# Connectors.net
KiCad netlist of a schematic drawn in Altium Designer
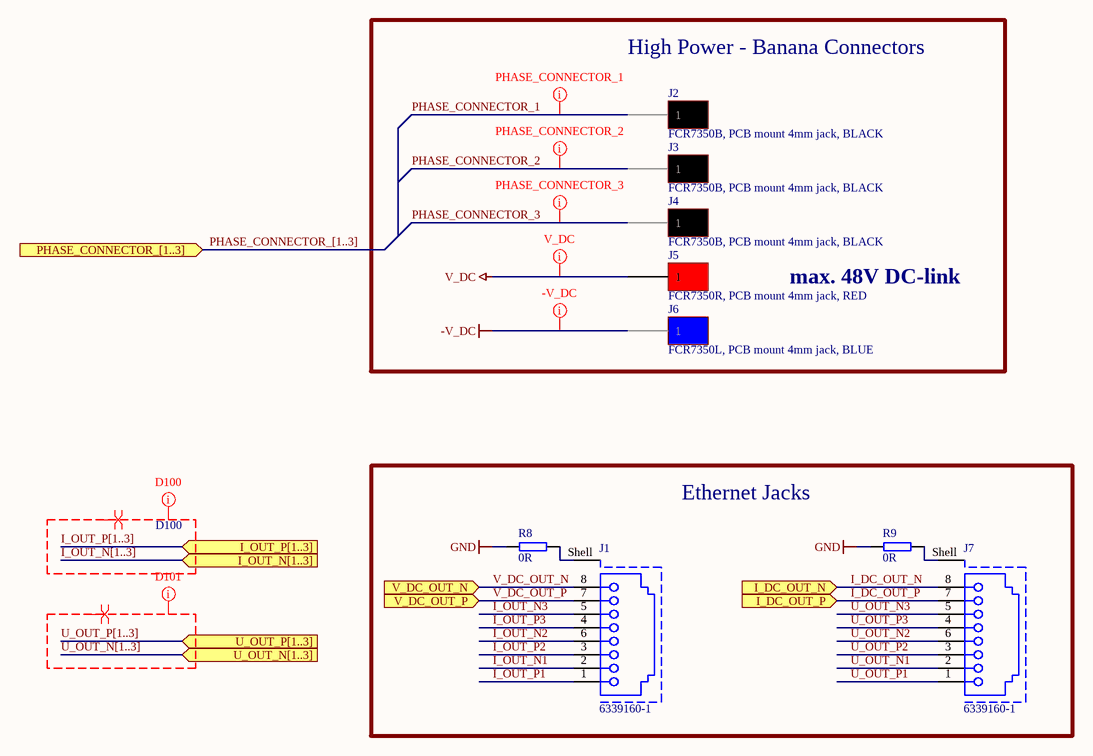
[diagram p0: Connectors.SchDoc]

(export (version "E")
  (design (tool "Eeschema 10.0.6"))
  (components
    (comp (ref "J1")
      (value "6339160-1")
      (footprint "634008149821")
      (fields
        (field (name "MANUFACTURER") "TE")
        (field (name "LCSC PART NUMBER") "C125076")
        (field (name "CREATED FROM") "NDiringer")
      )
      (libsource (lib "user") (part "634008149821"))
    )
    (comp (ref "J2")
      (value "FCR7350B, PCB mount 4mm jack, BLACK")
      (footprint "FCR7350")
      (description "FCR7350B, 1000V, 24A, BLACK")
      (fields
        (field (name "MANUFACTURER PART NUMBER") "FCR7350B")
        (field (name "MANUFACTURER") "Cliff")
        (field (name "CREATED FROM") "DHufnagel")
      )
      (libsource (lib "user") (part "FCR7350B"))
    )
    (comp (ref "J3")
      (value "FCR7350B, PCB mount 4mm jack, BLACK")
      (footprint "FCR7350")
      (description "FCR7350B, 1000V, 24A, BLACK")
      (fields
        (field (name "MANUFACTURER PART NUMBER") "FCR7350B")
        (field (name "MANUFACTURER") "Cliff")
        (field (name "CREATED FROM") "DHufnagel")
      )
      (libsource (lib "user") (part "FCR7350B"))
    )
    (comp (ref "J4")
      (value "FCR7350B, PCB mount 4mm jack, BLACK")
      (footprint "FCR7350")
      (description "FCR7350B, 1000V, 24A, BLACK")
      (fields
        (field (name "MANUFACTURER PART NUMBER") "FCR7350B")
        (field (name "MANUFACTURER") "Cliff")
        (field (name "CREATED FROM") "DHufnagel")
      )
      (libsource (lib "user") (part "FCR7350B"))
    )
    (comp (ref "J5")
      (value "FCR7350R, PCB mount 4mm jack, RED")
      (footprint "FCR7350")
      (description "FCR7350B, 1000V, 24A, RED")
      (fields
        (field (name "MANUFACTURER PART NUMBER") "FCR7350R")
        (field (name "MANUFACTURER") "Cliff")
        (field (name "CREATED FROM") "DHufnagel")
      )
      (libsource (lib "user") (part "FCR7350R"))
    )
    (comp (ref "J6")
      (value "FCR7350L, PCB mount 4mm jack, BLUE")
      (footprint "FCR7350")
      (description "FCR7350B, 1000V, 24A, BLUE")
      (fields
        (field (name "MANUFACTURER PART NUMBER") "FCR7350L")
        (field (name "MANUFACTURER") "Cliff")
        (field (name "CREATED FROM") "DHufnagel")
      )
      (libsource (lib "user") (part "FCR7350L"))
    )
    (comp (ref "J7")
      (value "6339160-1")
      (footprint "634008149821")
      (fields
        (field (name "MANUFACTURER") "TE")
        (field (name "LCSC PART NUMBER") "C125076")
        (field (name "CREATED FROM") "NDiringer")
      )
      (libsource (lib "user") (part "634008149821"))
    )
    (comp (ref "R8")
      (value "0R")
      (footprint "RES 0603_1608")
      (description "SMD resistor E24 series")
      (fields
        (field (name "MANUFACTURER PART NUMBER") "RC0603JR-070RL")
        (field (name "MANUFACTURER") "YAGEO")
        (field (name "CREATED FROM") "MGremer")
      )
      (libsource (lib "user") (part "Resistor"))
    )
    (comp (ref "R9")
      (value "0R")
      (footprint "RES 0603_1608")
      (description "SMD resistor E24 series")
      (fields
        (field (name "MANUFACTURER PART NUMBER") "RC0603JR-070RL")
        (field (name "MANUFACTURER") "YAGEO")
        (field (name "CREATED FROM") "MGremer")
      )
      (libsource (lib "user") (part "Resistor"))
    )
  )
  (nets
    (net (code "1") (name "-V_DC") (class "Default")
      (node (ref "J6") (pin "1") (pinfunction "1_1") (pintype "passive"))
    )
    (net (code "2") (name "/I_DC_OUT_N") (class "Default")
      (node (ref "J7") (pin "8") (pinfunction "8_8") (pintype "passive"))
    )
    (net (code "3") (name "/I_DC_OUT_P") (class "Default")
      (node (ref "J7") (pin "7") (pinfunction "7_7") (pintype "passive"))
    )
    (net (code "4") (name "/I_OUT_N1") (class "Default")
      (node (ref "J1") (pin "2") (pinfunction "2_2") (pintype "passive"))
    )
    (net (code "5") (name "/I_OUT_N2") (class "Default")
      (node (ref "J1") (pin "6") (pinfunction "6_6") (pintype "passive"))
    )
    (net (code "6") (name "/I_OUT_N3") (class "Default")
      (node (ref "J1") (pin "5") (pinfunction "5_5") (pintype "passive"))
    )
    (net (code "8") (name "/I_OUT_P1") (class "Default")
      (node (ref "J1") (pin "1") (pinfunction "1_1") (pintype "passive"))
    )
    (net (code "9") (name "/I_OUT_P2") (class "Default")
      (node (ref "J1") (pin "3") (pinfunction "3_3") (pintype "passive"))
    )
    (net (code "10") (name "/I_OUT_P3") (class "Default")
      (node (ref "J1") (pin "4") (pinfunction "4_4") (pintype "passive"))
    )
    (net (code "12") (name "/PHASE_CONNECTOR_1") (class "Default")
      (node (ref "J2") (pin "1") (pinfunction "1_1") (pintype "passive"))
    )
    (net (code "13") (name "/PHASE_CONNECTOR_2") (class "Default")
      (node (ref "J3") (pin "1") (pinfunction "1_1") (pintype "passive"))
    )
    (net (code "14") (name "/PHASE_CONNECTOR_3") (class "Default")
      (node (ref "J4") (pin "1") (pinfunction "1_1") (pintype "passive"))
    )
    (net (code "16") (name "/U_OUT_N1") (class "Default")
      (node (ref "J7") (pin "2") (pinfunction "2_2") (pintype "passive"))
    )
    (net (code "17") (name "/U_OUT_N2") (class "Default")
      (node (ref "J7") (pin "6") (pinfunction "6_6") (pintype "passive"))
    )
    (net (code "18") (name "/U_OUT_N3") (class "Default")
      (node (ref "J7") (pin "5") (pinfunction "5_5") (pintype "passive"))
    )
    (net (code "20") (name "/U_OUT_P1") (class "Default")
      (node (ref "J7") (pin "1") (pinfunction "1_1") (pintype "passive"))
    )
    (net (code "21") (name "/U_OUT_P2") (class "Default")
      (node (ref "J7") (pin "3") (pinfunction "3_3") (pintype "passive"))
    )
    (net (code "22") (name "/U_OUT_P3") (class "Default")
      (node (ref "J7") (pin "4") (pinfunction "4_4") (pintype "passive"))
    )
    (net (code "24") (name "/V_DC_OUT_N") (class "Default")
      (node (ref "J1") (pin "8") (pinfunction "8_8") (pintype "passive"))
    )
    (net (code "25") (name "/V_DC_OUT_P") (class "Default")
      (node (ref "J1") (pin "7") (pinfunction "7_7") (pintype "passive"))
    )
    (net (code "26") (name "GND") (class "Default")
      (node (ref "R8") (pin "1") (pinfunction "1_1") (pintype "passive"))
      (node (ref "R9") (pin "1") (pinfunction "1_1") (pintype "passive"))
    )
    (net (code "27") (name "Net-(J1-PadShell)") (class "Default")
      (node (ref "J1") (pin "Shell") (pinfunction "Shell_Shell") (pintype "passive"))
      (node (ref "R8") (pin "2") (pinfunction "2_2") (pintype "passive"))
    )
    (net (code "28") (name "Net-(J7-PadShell)") (class "Default")
      (node (ref "J7") (pin "Shell") (pinfunction "Shell_Shell") (pintype "passive"))
      (node (ref "R9") (pin "2") (pinfunction "2_2") (pintype "passive"))
    )
    (net (code "29") (name "V_DC") (class "Default")
      (node (ref "J5") (pin "1") (pinfunction "1_1") (pintype "passive"))
    )
  )
)
